# Grove_-_Triple_Color_E-Ink_Display_2_13.net
KiCad netlist of a schematic drawn in EAGLE
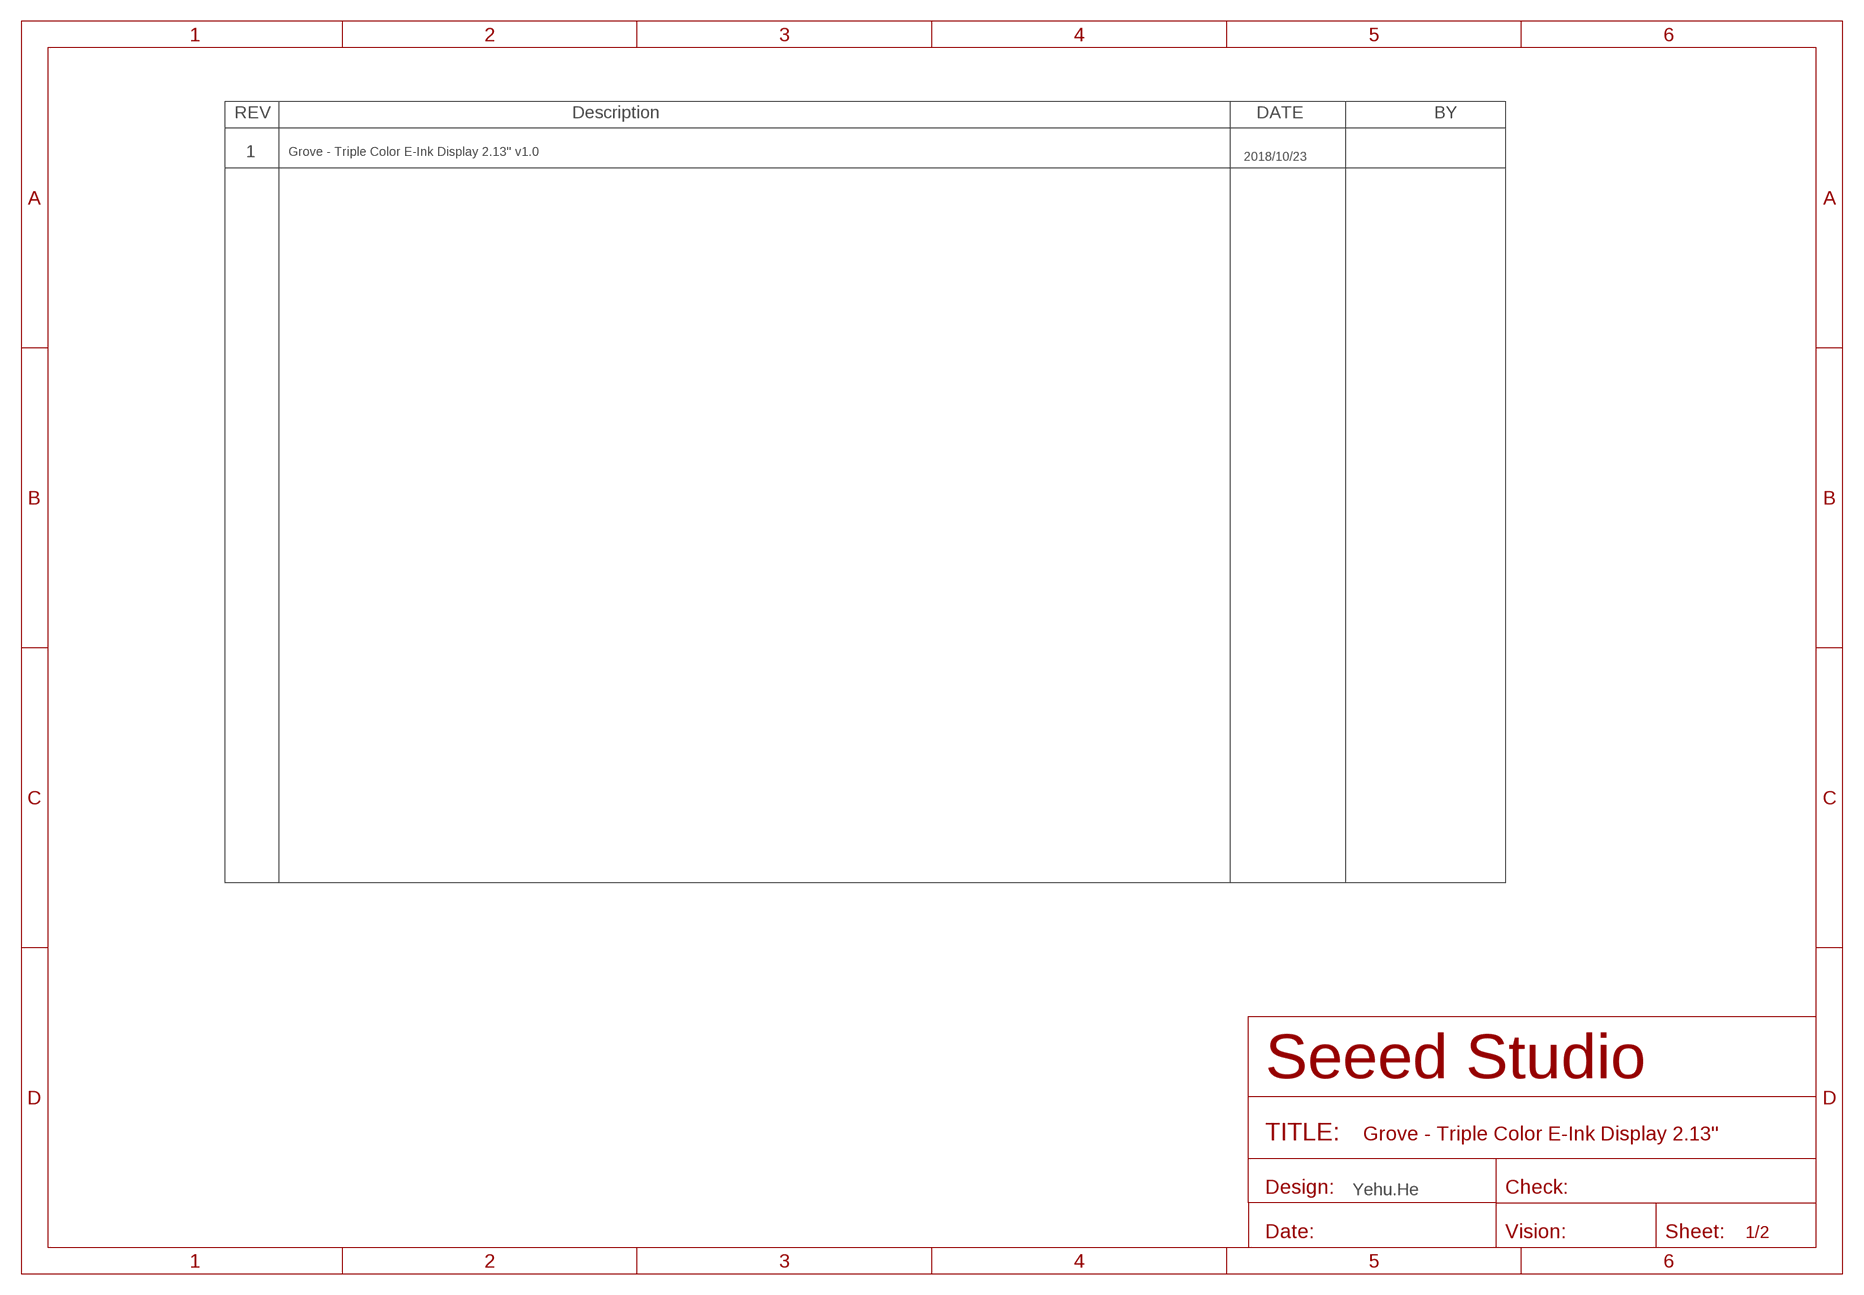
[diagram p0: schematic, sheet 1]
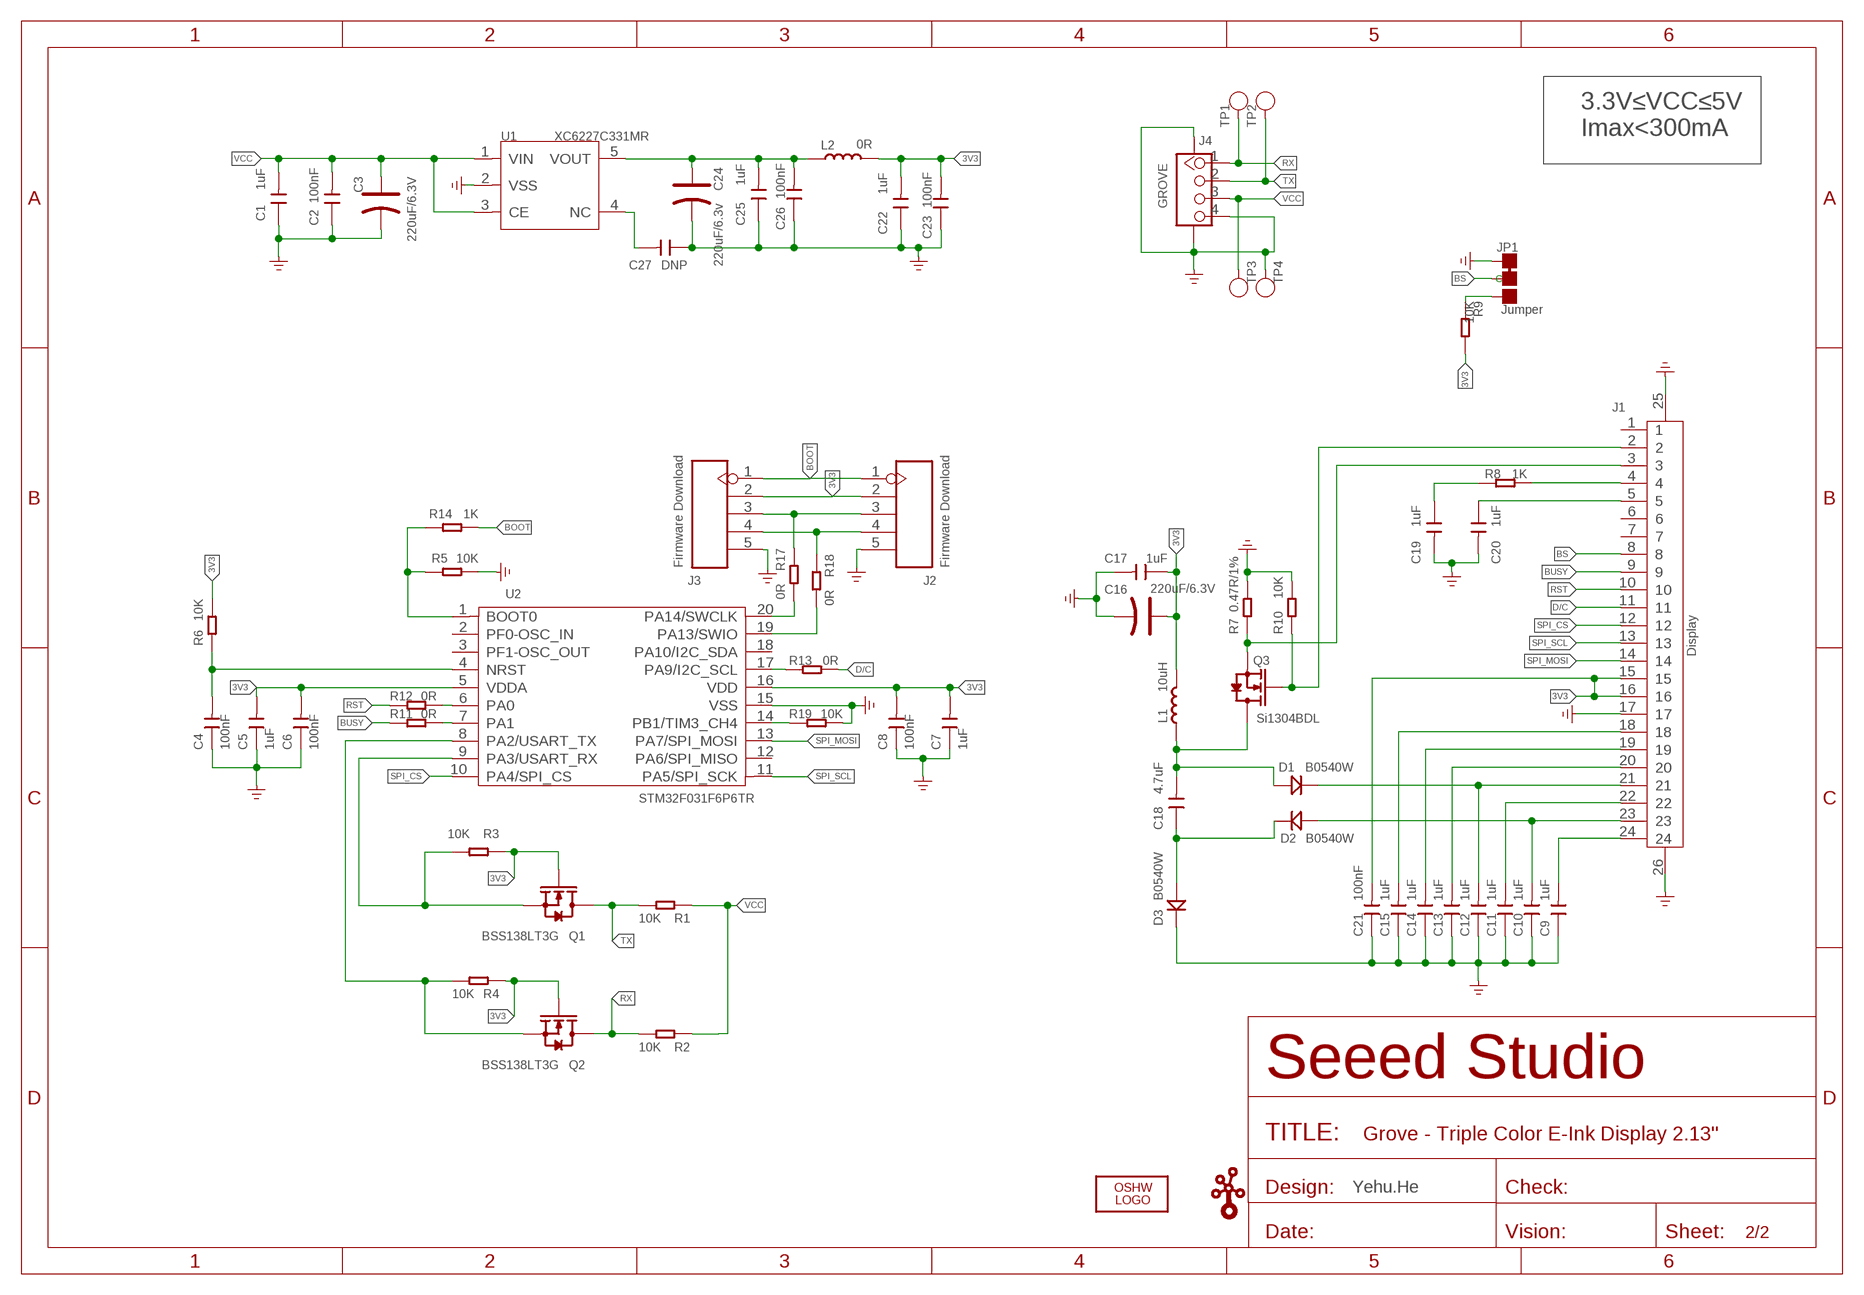
[diagram p1: schematic, sheet 2]

(export (version "E")
  (design (tool "Eeschema 10.0.6"))
  (components
    (comp (ref "C1")
      (value "1uF")
      (footprint "eagle-import:C0603")
      (libsource (lib "eagle-import") (part "CAP-0603"))
    )
    (comp (ref "C2")
      (value "100nF")
      (footprint "eagle-import:C0603")
      (libsource (lib "eagle-import") (part "CAP-0603"))
    )
    (comp (ref "C3")
      (value "220uF/6.3V")
      (footprint "eagle-import:AVX-B")
      (libsource (lib "eagle-import") (part "CAP-POLAR-AVX-B"))
    )
    (comp (ref "C4")
      (value "100nF")
      (footprint "eagle-import:C0603")
      (libsource (lib "eagle-import") (part "CAP-0603"))
    )
    (comp (ref "C5")
      (value "1uF")
      (footprint "eagle-import:C0603")
      (libsource (lib "eagle-import") (part "CAP-0603"))
    )
    (comp (ref "C6")
      (value "100nF")
      (footprint "eagle-import:C0603")
      (libsource (lib "eagle-import") (part "CAP-0603"))
    )
    (comp (ref "C7")
      (value "1uF")
      (footprint "eagle-import:C0603")
      (libsource (lib "eagle-import") (part "CAP-0603"))
    )
    (comp (ref "C8")
      (value "100nF")
      (footprint "eagle-import:C0603")
      (libsource (lib "eagle-import") (part "CAP-0603"))
    )
    (comp (ref "C9")
      (value "1uF")
      (footprint "eagle-import:C0603")
      (libsource (lib "eagle-import") (part "CAP-0603"))
    )
    (comp (ref "C10")
      (value "1uF")
      (footprint "eagle-import:C0603")
      (libsource (lib "eagle-import") (part "CAP-0603"))
    )
    (comp (ref "C11")
      (value "1uF")
      (footprint "eagle-import:C0603")
      (libsource (lib "eagle-import") (part "CAP-0603"))
    )
    (comp (ref "C12")
      (value "1uF")
      (footprint "eagle-import:C0603")
      (libsource (lib "eagle-import") (part "CAP-0603"))
    )
    (comp (ref "C13")
      (value "1uF")
      (footprint "eagle-import:C0603")
      (libsource (lib "eagle-import") (part "CAP-0603"))
    )
    (comp (ref "C14")
      (value "1uF")
      (footprint "eagle-import:C0603")
      (libsource (lib "eagle-import") (part "CAP-0603"))
    )
    (comp (ref "C15")
      (value "1uF")
      (footprint "eagle-import:C0603")
      (libsource (lib "eagle-import") (part "CAP-0603"))
    )
    (comp (ref "C16")
      (value "220uF/6.3V")
      (footprint "eagle-import:AVX-B")
      (libsource (lib "eagle-import") (part "CAP-POLAR-AVX-B"))
    )
    (comp (ref "C17")
      (value "1uF")
      (footprint "eagle-import:C0603")
      (libsource (lib "eagle-import") (part "CAP-0603"))
    )
    (comp (ref "C18")
      (value "4.7uF")
      (footprint "eagle-import:C0805")
      (libsource (lib "eagle-import") (part "CAP-0805"))
    )
    (comp (ref "C19")
      (value "1uF")
      (footprint "eagle-import:C0603")
      (libsource (lib "eagle-import") (part "CAP-0603"))
    )
    (comp (ref "C20")
      (value "1uF")
      (footprint "eagle-import:C0603")
      (libsource (lib "eagle-import") (part "CAP-0603"))
    )
    (comp (ref "C21")
      (value "100nF")
      (footprint "eagle-import:C0603")
      (libsource (lib "eagle-import") (part "CAP-0603"))
    )
    (comp (ref "C22")
      (value "1uF")
      (footprint "eagle-import:C0805")
      (libsource (lib "eagle-import") (part "CAP-0805"))
    )
    (comp (ref "C23")
      (value "100nF")
      (footprint "eagle-import:C0603")
      (libsource (lib "eagle-import") (part "CAP-0603"))
    )
    (comp (ref "C24")
      (value "220uF/6.3v")
      (footprint "eagle-import:AVX-B")
      (libsource (lib "eagle-import") (part "CAP-POLAR-AVX-B"))
    )
    (comp (ref "C25")
      (value "1uF")
      (footprint "eagle-import:C0805")
      (libsource (lib "eagle-import") (part "CAP-0805"))
    )
    (comp (ref "C26")
      (value "100nF")
      (footprint "eagle-import:C0603")
      (libsource (lib "eagle-import") (part "CAP-0603"))
    )
    (comp (ref "C27")
      (value "DNP")
      (footprint "eagle-import:C0603")
      (libsource (lib "eagle-import") (part "CAP-0603"))
    )
    (comp (ref "D1")
      (value "B0540W")
      (footprint "eagle-import:SOD-323")
      (libsource (lib "eagle-import") (part "DIODE'0805'"))
    )
    (comp (ref "D2")
      (value "B0540W")
      (footprint "eagle-import:SOD-323")
      (libsource (lib "eagle-import") (part "DIODE'0805'"))
    )
    (comp (ref "D3")
      (value "B0540W")
      (footprint "eagle-import:SOD-323")
      (libsource (lib "eagle-import") (part "DIODE'0805'"))
    )
    (comp (ref "J1")
      (value "Display")
      (footprint "eagle-import:FPCB24-SMD-0.5-17.6X5.0X2MM")
      (libsource (lib "eagle-import") (part "FPC-CONNECTOR-24P"))
    )
    (comp (ref "J2")
      (value "Firmware Download")
      (footprint "eagle-import:H5-SMD-2.54")
      (libsource (lib "eagle-import") (part "HEADER-5P-SMD2.54"))
    )
    (comp (ref "J3")
      (value "Firmware Download")
      (footprint "eagle-import:H5-SMD-2.54")
      (libsource (lib "eagle-import") (part "HEADER-5P-SMD2.54"))
    )
    (comp (ref "J4")
      (value "GROVE")
      (footprint "eagle-import:HW4-SMD-2.0-90D")
      (libsource (lib "eagle-import") (part "GROVE-CONNECTOR-SMD'90D'"))
    )
    (comp (ref "JP1")
      (value "Jumper")
      (footprint "eagle-import:3P-SMD-SHORT")
      (libsource (lib "eagle-import") (part "JP-3P-SHORT"))
    )
    (comp (ref "L1")
      (value "10uH")
      (footprint "eagle-import:L5040S")
      (libsource (lib "eagle-import") (part "INDUCTOR/FERRITE-BEAD5040S"))
    )
    (comp (ref "L2")
      (value "0R")
      (footprint "eagle-import:L0805")
      (libsource (lib "eagle-import") (part "INDUCTOR/FERRITE-BEAD'0805'"))
    )
    (comp (ref "LOGO2")
      (value "LOGO-OSHW-FILLX0200-NT")
      (footprint "eagle-import:OSHW_FILLX200_NOTEXT")
      (fields (field (name "PARTNO") "DNP"))
      (libsource (lib "eagle-import") (part "LOGO-OSHW-FILLX0200-NT"))
    )
    (comp (ref "Q1")
      (value "BSS138LT3G")
      (footprint "eagle-import:SOT-323")
      (libsource (lib "eagle-import") (part "MOSFET-N'SI1304BDL'"))
    )
    (comp (ref "Q2")
      (value "BSS138LT3G")
      (footprint "eagle-import:SOT-323")
      (libsource (lib "eagle-import") (part "MOSFET-N'SI1304BDL'"))
    )
    (comp (ref "Q3")
      (value "Si1304BDL")
      (footprint "eagle-import:SOT-323")
      (libsource (lib "eagle-import") (part "MOSFET-N'SI1304BDL'"))
    )
    (comp (ref "R1")
      (value "10K")
      (footprint "eagle-import:R0603")
      (libsource (lib "eagle-import") (part "RES-0603"))
    )
    (comp (ref "R2")
      (value "10K")
      (footprint "eagle-import:R0603")
      (libsource (lib "eagle-import") (part "RES-0603"))
    )
    (comp (ref "R3")
      (value "10K")
      (footprint "eagle-import:R0603")
      (libsource (lib "eagle-import") (part "RES-0603"))
    )
    (comp (ref "R4")
      (value "10K")
      (footprint "eagle-import:R0603")
      (libsource (lib "eagle-import") (part "RES-0603"))
    )
    (comp (ref "R5")
      (value "10K")
      (footprint "eagle-import:R0603")
      (libsource (lib "eagle-import") (part "RES-0603"))
    )
    (comp (ref "R6")
      (value "10K")
      (footprint "eagle-import:R0603")
      (libsource (lib "eagle-import") (part "RES-0603"))
    )
    (comp (ref "R7")
      (value "0.47R/1%")
      (footprint "eagle-import:R0603")
      (libsource (lib "eagle-import") (part "RES-0603"))
    )
    (comp (ref "R8")
      (value "1K")
      (footprint "eagle-import:R0603")
      (libsource (lib "eagle-import") (part "RES-0603"))
    )
    (comp (ref "R9")
      (value "10K")
      (footprint "eagle-import:R0603")
      (libsource (lib "eagle-import") (part "RES-0603"))
    )
    (comp (ref "R10")
      (value "10K")
      (footprint "eagle-import:R0603")
      (libsource (lib "eagle-import") (part "RES-0603"))
    )
    (comp (ref "R11")
      (value "0R")
      (footprint "eagle-import:R0603")
      (libsource (lib "eagle-import") (part "RES-0603"))
    )
    (comp (ref "R12")
      (value "0R")
      (footprint "eagle-import:R0603")
      (libsource (lib "eagle-import") (part "RES-0603"))
    )
    (comp (ref "R13")
      (value "0R")
      (footprint "eagle-import:R0603")
      (libsource (lib "eagle-import") (part "RES-0603"))
    )
    (comp (ref "R14")
      (value "1K")
      (footprint "eagle-import:R0603")
      (libsource (lib "eagle-import") (part "RES-0603"))
    )
    (comp (ref "R17")
      (value "0R")
      (footprint "eagle-import:R0603")
      (libsource (lib "eagle-import") (part "RES-0603"))
    )
    (comp (ref "R18")
      (value "0R")
      (footprint "eagle-import:R0603")
      (libsource (lib "eagle-import") (part "RES-0603"))
    )
    (comp (ref "R19")
      (value "10K")
      (footprint "eagle-import:R0603")
      (libsource (lib "eagle-import") (part "RES-0603"))
    )
    (comp (ref "TP1")
      (value "Test")
      (footprint "eagle-import:TP-D45MIL")
      (fields (field (name "PARTNO") "DNP"))
      (libsource (lib "eagle-import") (part "TEST-POINT'4545'"))
    )
    (comp (ref "TP2")
      (value "Test")
      (footprint "eagle-import:TP-D45MIL")
      (fields (field (name "PARTNO") "DNP"))
      (libsource (lib "eagle-import") (part "TEST-POINT'4545'"))
    )
    (comp (ref "TP3")
      (value "Test")
      (footprint "eagle-import:TP-D45MIL")
      (fields (field (name "PARTNO") "DNP"))
      (libsource (lib "eagle-import") (part "TEST-POINT'4545'"))
    )
    (comp (ref "TP4")
      (value "Test")
      (footprint "eagle-import:TP-D45MIL")
      (fields (field (name "PARTNO") "DNP"))
      (libsource (lib "eagle-import") (part "TEST-POINT'4545'"))
    )
    (comp (ref "U$20")
      (value "LOGO-GROVE")
      (footprint "eagle-import:GROVE-SILK-BIG")
      (fields (field (name "PARTNO") "DNP"))
      (libsource (lib "eagle-import") (part "LOGO-GROVE"))
    )
    (comp (ref "U1")
      (value "XC6227C331MR")
      (footprint "eagle-import:SOT-23-5")
      (libsource (lib "eagle-import") (part "PMIC-LDO-XC6210"))
    )
    (comp (ref "U2")
      (value "STM32F031F6P6TR")
      (footprint "eagle-import:TSSOP20-0.65-6.5X4.4MM")
      (libsource (lib "eagle-import") (part "MCU-STM32F030"))
    )
  )
  (nets
    (net (code "1") (name "3V3") (class "Default")
      (node (ref "C16") (pin "+") (pinfunction "+_+") (pintype "passive"))
      (node (ref "C17") (pin "1") (pinfunction "1_1") (pintype "passive"))
      (node (ref "C21") (pin "2") (pinfunction "2_2") (pintype "passive"))
      (node (ref "C22") (pin "2") (pinfunction "2_2") (pintype "passive"))
      (node (ref "C23") (pin "2") (pinfunction "2_2") (pintype "passive"))
      (node (ref "C5") (pin "2") (pinfunction "2_2") (pintype "passive"))
      (node (ref "C6") (pin "2") (pinfunction "2_2") (pintype "passive"))
      (node (ref "C7") (pin "2") (pinfunction "2_2") (pintype "passive"))
      (node (ref "C8") (pin "2") (pinfunction "2_2") (pintype "passive"))
      (node (ref "J1") (pin "15") (pinfunction "15_15") (pintype "bidirectional"))
      (node (ref "J1") (pin "16") (pinfunction "16_16") (pintype "bidirectional"))
      (node (ref "J2") (pin "2") (pinfunction "2_2") (pintype "bidirectional"))
      (node (ref "J3") (pin "2") (pinfunction "2_2") (pintype "bidirectional"))
      (node (ref "L1") (pin "2") (pinfunction "2_2") (pintype "passive"))
      (node (ref "L2") (pin "2") (pinfunction "2_2") (pintype "passive"))
      (node (ref "Q1") (pin "1") (pinfunction "G_1") (pintype "passive"))
      (node (ref "Q2") (pin "1") (pinfunction "G_1") (pintype "passive"))
      (node (ref "R3") (pin "2") (pinfunction "2_2") (pintype "passive"))
      (node (ref "R4") (pin "2") (pinfunction "2_2") (pintype "passive"))
      (node (ref "R6") (pin "1") (pinfunction "1_1") (pintype "passive"))
      (node (ref "R9") (pin "2") (pinfunction "2_2") (pintype "passive"))
      (node (ref "U2") (pin "16") (pinfunction "VDD_16") (pintype "bidirectional"))
      (node (ref "U2") (pin "5") (pinfunction "VDDA_5") (pintype "bidirectional"))
    )
    (net (code "2") (name "BOOT") (class "Default")
      (node (ref "J2") (pin "1") (pinfunction "1_1") (pintype "bidirectional"))
      (node (ref "J3") (pin "1") (pinfunction "1_1") (pintype "bidirectional"))
      (node (ref "R14") (pin "1") (pinfunction "1_1") (pintype "passive"))
    )
    (net (code "3") (name "BS") (class "Default")
      (node (ref "J1") (pin "8") (pinfunction "8_8") (pintype "bidirectional"))
      (node (ref "JP1") (pin "MM") (pinfunction "C_MM") (pintype "bidirectional"))
    )
    (net (code "4") (name "BUSY") (class "Default")
      (node (ref "J1") (pin "9") (pinfunction "9_9") (pintype "bidirectional"))
      (node (ref "R11") (pin "1") (pinfunction "1_1") (pintype "passive"))
    )
    (net (code "5") (name "D{slash}C") (class "Default")
      (node (ref "J1") (pin "11") (pinfunction "11_11") (pintype "bidirectional"))
      (node (ref "R13") (pin "1") (pinfunction "1_1") (pintype "passive"))
    )
    (net (code "6") (name "GND") (class "Default")
      (node (ref "C1") (pin "1") (pinfunction "1_1") (pintype "passive"))
      (node (ref "C10") (pin "1") (pinfunction "1_1") (pintype "passive"))
      (node (ref "C11") (pin "1") (pinfunction "1_1") (pintype "passive"))
      (node (ref "C12") (pin "1") (pinfunction "1_1") (pintype "passive"))
      (node (ref "C13") (pin "1") (pinfunction "1_1") (pintype "passive"))
      (node (ref "C14") (pin "1") (pinfunction "1_1") (pintype "passive"))
      (node (ref "C15") (pin "1") (pinfunction "1_1") (pintype "passive"))
      (node (ref "C16") (pin "-") (pinfunction "-_-") (pintype "passive"))
      (node (ref "C17") (pin "2") (pinfunction "2_2") (pintype "passive"))
      (node (ref "C19") (pin "2") (pinfunction "2_2") (pintype "passive"))
      (node (ref "C2") (pin "1") (pinfunction "1_1") (pintype "passive"))
      (node (ref "C20") (pin "2") (pinfunction "2_2") (pintype "passive"))
      (node (ref "C21") (pin "1") (pinfunction "1_1") (pintype "passive"))
      (node (ref "C22") (pin "1") (pinfunction "1_1") (pintype "passive"))
      (node (ref "C23") (pin "1") (pinfunction "1_1") (pintype "passive"))
      (node (ref "C24") (pin "-") (pinfunction "-_-") (pintype "passive"))
      (node (ref "C25") (pin "1") (pinfunction "1_1") (pintype "passive"))
      (node (ref "C26") (pin "1") (pinfunction "1_1") (pintype "passive"))
      (node (ref "C27") (pin "1") (pinfunction "1_1") (pintype "passive"))
      (node (ref "C3") (pin "-") (pinfunction "-_-") (pintype "passive"))
      (node (ref "C4") (pin "1") (pinfunction "1_1") (pintype "passive"))
      (node (ref "C5") (pin "1") (pinfunction "1_1") (pintype "passive"))
      (node (ref "C6") (pin "1") (pinfunction "1_1") (pintype "passive"))
      (node (ref "C7") (pin "1") (pinfunction "1_1") (pintype "passive"))
      (node (ref "C8") (pin "1") (pinfunction "1_1") (pintype "passive"))
      (node (ref "C9") (pin "1") (pinfunction "1_1") (pintype "passive"))
      (node (ref "D3") (pin "-") (pinfunction "-_-") (pintype "passive"))
      (node (ref "J1") (pin "17") (pinfunction "17_17") (pintype "bidirectional"))
      (node (ref "J1") (pin "25") (pinfunction "P1_25") (pintype "bidirectional"))
      (node (ref "J1") (pin "26") (pinfunction "P2_26") (pintype "bidirectional"))
      (node (ref "J2") (pin "5") (pinfunction "5_5") (pintype "bidirectional"))
      (node (ref "J3") (pin "5") (pinfunction "5_5") (pintype "bidirectional"))
      (node (ref "J4") (pin "4") (pinfunction "4_4") (pintype "bidirectional"))
      (node (ref "J4") (pin "SS1") (pinfunction "SS1_SS1") (pintype "bidirectional"))
      (node (ref "J4") (pin "SS2") (pinfunction "SS2_SS2") (pintype "bidirectional"))
      (node (ref "JP1") (pin "11") (pinfunction "L_11") (pintype "bidirectional"))
      (node (ref "R10") (pin "2") (pinfunction "2_2") (pintype "passive"))
      (node (ref "R19") (pin "1") (pinfunction "1_1") (pintype "passive"))
      (node (ref "R5") (pin "1") (pinfunction "1_1") (pintype "passive"))
      (node (ref "R7") (pin "2") (pinfunction "2_2") (pintype "passive"))
      (node (ref "TP4") (pin "T") (pinfunction "T_T") (pintype "bidirectional"))
      (node (ref "U1") (pin "2") (pinfunction "VSS_2") (pintype "bidirectional"))
      (node (ref "U2") (pin "15") (pinfunction "VSS_15") (pintype "bidirectional"))
    )
    (net (code "7") (name "Net-(C9-Pad2)") (class "Default")
      (node (ref "C9") (pin "2") (pinfunction "2_2") (pintype "passive"))
      (node (ref "J1") (pin "24") (pinfunction "24_24") (pintype "bidirectional"))
    )
    (net (code "8") (name "Net-(C10-Pad2)") (class "Default")
      (node (ref "C10") (pin "2") (pinfunction "2_2") (pintype "passive"))
      (node (ref "D2") (pin "+") (pinfunction "+_+") (pintype "passive"))
      (node (ref "J1") (pin "23") (pinfunction "23_23") (pintype "bidirectional"))
    )
    (net (code "9") (name "Net-(C11-Pad2)") (class "Default")
      (node (ref "C11") (pin "2") (pinfunction "2_2") (pintype "passive"))
      (node (ref "J1") (pin "22") (pinfunction "22_22") (pintype "bidirectional"))
    )
    (net (code "10") (name "Net-(C12-Pad2)") (class "Default")
      (node (ref "C12") (pin "2") (pinfunction "2_2") (pintype "passive"))
      (node (ref "D1") (pin "-") (pinfunction "-_-") (pintype "passive"))
      (node (ref "J1") (pin "21") (pinfunction "21_21") (pintype "bidirectional"))
    )
    (net (code "11") (name "Net-(C13-Pad2)") (class "Default")
      (node (ref "C13") (pin "2") (pinfunction "2_2") (pintype "passive"))
      (node (ref "J1") (pin "20") (pinfunction "20_20") (pintype "bidirectional"))
    )
    (net (code "12") (name "Net-(C14-Pad2)") (class "Default")
      (node (ref "C14") (pin "2") (pinfunction "2_2") (pintype "passive"))
      (node (ref "J1") (pin "19") (pinfunction "19_19") (pintype "bidirectional"))
    )
    (net (code "13") (name "Net-(C15-Pad2)") (class "Default")
      (node (ref "C15") (pin "2") (pinfunction "2_2") (pintype "passive"))
      (node (ref "J1") (pin "18") (pinfunction "18_18") (pintype "bidirectional"))
    )
    (net (code "14") (name "Net-(C18-Pad1)") (class "Default")
      (node (ref "C18") (pin "1") (pinfunction "1_1") (pintype "passive"))
      (node (ref "D2") (pin "-") (pinfunction "-_-") (pintype "passive"))
      (node (ref "D3") (pin "+") (pinfunction "+_+") (pintype "passive"))
    )
    (net (code "15") (name "Net-(C19-Pad1)") (class "Default")
      (node (ref "C19") (pin "1") (pinfunction "1_1") (pintype "passive"))
      (node (ref "R8") (pin "2") (pinfunction "2_2") (pintype "passive"))
    )
    (net (code "16") (name "Net-(C20-Pad1)") (class "Default")
      (node (ref "C20") (pin "1") (pinfunction "1_1") (pintype "passive"))
      (node (ref "J1") (pin "5") (pinfunction "5_5") (pintype "bidirectional"))
    )
    (net (code "17") (name "Net-(J1-Pad4)") (class "Default")
      (node (ref "J1") (pin "4") (pinfunction "4_4") (pintype "bidirectional"))
      (node (ref "R8") (pin "1") (pinfunction "1_1") (pintype "passive"))
    )
    (net (code "18") (name "Net-(J2-Pad3)") (class "Default")
      (node (ref "J2") (pin "3") (pinfunction "3_3") (pintype "bidirectional"))
      (node (ref "J3") (pin "3") (pinfunction "3_3") (pintype "bidirectional"))
      (node (ref "R17") (pin "1") (pinfunction "1_1") (pintype "passive"))
    )
    (net (code "19") (name "Net-(J2-Pad4)") (class "Default")
      (node (ref "J2") (pin "4") (pinfunction "4_4") (pintype "bidirectional"))
      (node (ref "J3") (pin "4") (pinfunction "4_4") (pintype "bidirectional"))
      (node (ref "R18") (pin "1") (pinfunction "1_1") (pintype "passive"))
    )
    (net (code "20") (name "Net-(JP1-R)") (class "Default")
      (node (ref "JP1") (pin "00") (pinfunction "R_00") (pintype "bidirectional"))
      (node (ref "R9") (pin "1") (pinfunction "1_1") (pintype "passive"))
    )
    (net (code "21") (name "Net-(Q1-S)") (class "Default")
      (node (ref "Q1") (pin "2") (pinfunction "S_2") (pintype "passive"))
      (node (ref "R3") (pin "1") (pinfunction "1_1") (pintype "passive"))
      (node (ref "U2") (pin "9") (pinfunction "PA3/USART_RX_9") (pintype "bidirectional"))
    )
    (net (code "22") (name "Net-(Q2-S)") (class "Default")
      (node (ref "Q2") (pin "2") (pinfunction "S_2") (pintype "passive"))
      (node (ref "R4") (pin "1") (pinfunction "1_1") (pintype "passive"))
      (node (ref "U2") (pin "8") (pinfunction "PA2/USART_TX_8") (pintype "bidirectional"))
    )
    (net (code "23") (name "Net-(Q3-D)") (class "Default")
      (node (ref "C18") (pin "2") (pinfunction "2_2") (pintype "passive"))
      (node (ref "D1") (pin "+") (pinfunction "+_+") (pintype "passive"))
      (node (ref "L1") (pin "1") (pinfunction "1_1") (pintype "passive"))
      (node (ref "Q3") (pin "3") (pinfunction "D_3") (pintype "passive"))
    )
    (net (code "24") (name "Net-(Q3-G)") (class "Default")
      (node (ref "J1") (pin "2") (pinfunction "2_2") (pintype "bidirectional"))
      (node (ref "Q3") (pin "1") (pinfunction "G_1") (pintype "passive"))
      (node (ref "R10") (pin "1") (pinfunction "1_1") (pintype "passive"))
    )
    (net (code "25") (name "Net-(Q3-S)") (class "Default")
      (node (ref "J1") (pin "3") (pinfunction "3_3") (pintype "bidirectional"))
      (node (ref "Q3") (pin "2") (pinfunction "S_2") (pintype "passive"))
      (node (ref "R7") (pin "1") (pinfunction "1_1") (pintype "passive"))
    )
    (net (code "26") (name "Net-(U1-NC)") (class "Default")
      (node (ref "C27") (pin "2") (pinfunction "2_2") (pintype "passive"))
      (node (ref "U1") (pin "4") (pinfunction "NC_4") (pintype "bidirectional"))
    )
    (net (code "27") (name "Net-(U1-VOUT)") (class "Default")
      (node (ref "C24") (pin "+") (pinfunction "+_+") (pintype "passive"))
      (node (ref "C25") (pin "2") (pinfunction "2_2") (pintype "passive"))
      (node (ref "C26") (pin "2") (pinfunction "2_2") (pintype "passive"))
      (node (ref "L2") (pin "1") (pinfunction "1_1") (pintype "passive"))
      (node (ref "U1") (pin "5") (pinfunction "VOUT_5") (pintype "bidirectional"))
    )
    (net (code "28") (name "Net-(U2-BOOT0)") (class "Default")
      (node (ref "R14") (pin "2") (pinfunction "2_2") (pintype "passive"))
      (node (ref "R5") (pin "2") (pinfunction "2_2") (pintype "passive"))
      (node (ref "U2") (pin "1") (pinfunction "BOOT0_1") (pintype "bidirectional"))
    )
    (net (code "29") (name "Net-(U2-NRST)") (class "Default")
      (node (ref "C4") (pin "2") (pinfunction "2_2") (pintype "passive"))
      (node (ref "R6") (pin "2") (pinfunction "2_2") (pintype "passive"))
      (node (ref "U2") (pin "4") (pinfunction "NRST_4") (pintype "bidirectional"))
    )
    (net (code "30") (name "Net-(U2-PA0)") (class "Default")
      (node (ref "R12") (pin "2") (pinfunction "2_2") (pintype "passive"))
      (node (ref "U2") (pin "6") (pinfunction "PA0_6") (pintype "bidirectional"))
    )
    (net (code "31") (name "Net-(U2-PA1)") (class "Default")
      (node (ref "R11") (pin "2") (pinfunction "2_2") (pintype "passive"))
      (node (ref "U2") (pin "7") (pinfunction "PA1_7") (pintype "bidirectional"))
    )
    (net (code "32") (name "Net-(U2-PA9{slash}I2C_SCL)") (class "Default")
      (node (ref "R13") (pin "2") (pinfunction "2_2") (pintype "passive"))
      (node (ref "U2") (pin "17") (pinfunction "PA9/I2C_SCL_17") (pintype "bidirectional"))
    )
    (net (code "33") (name "Net-(U2-PA13{slash}SWIO)") (class "Default")
      (node (ref "R18") (pin "2") (pinfunction "2_2") (pintype "passive"))
      (node (ref "U2") (pin "19") (pinfunction "PA13/SWIO_19") (pintype "bidirectional"))
    )
    (net (code "34") (name "Net-(U2-PA14{slash}SWCLK)") (class "Default")
      (node (ref "R17") (pin "2") (pinfunction "2_2") (pintype "passive"))
      (node (ref "U2") (pin "20") (pinfunction "PA14/SWCLK_20") (pintype "bidirectional"))
    )
    (net (code "35") (name "Net-(U2-PB1{slash}TIM3_CH4)") (class "Default")
      (node (ref "R19") (pin "2") (pinfunction "2_2") (pintype "passive"))
      (node (ref "U2") (pin "14") (pinfunction "PB1/TIM3_CH4_14") (pintype "bidirectional"))
    )
    (net (code "36") (name "RST") (class "Default")
      (node (ref "J1") (pin "10") (pinfunction "10_10") (pintype "bidirectional"))
      (node (ref "R12") (pin "1") (pinfunction "1_1") (pintype "passive"))
    )
    (net (code "37") (name "RX") (class "Default")
      (node (ref "J4") (pin "1") (pinfunction "1_1") (pintype "bidirectional"))
      (node (ref "Q2") (pin "3") (pinfunction "D_3") (pintype "passive"))
      (node (ref "R2") (pin "1") (pinfunction "1_1") (pintype "passive"))
      (node (ref "TP1") (pin "T") (pinfunction "T_T") (pintype "bidirectional"))
    )
    (net (code "38") (name "SPI_CS") (class "Default")
      (node (ref "J1") (pin "12") (pinfunction "12_12") (pintype "bidirectional"))
      (node (ref "U2") (pin "10") (pinfunction "PA4/SPI_CS_10") (pintype "bidirectional"))
    )
    (net (code "39") (name "SPI_MOSI") (class "Default")
      (node (ref "J1") (pin "14") (pinfunction "14_14") (pintype "bidirectional"))
      (node (ref "U2") (pin "13") (pinfunction "PA7/SPI_MOSI_13") (pintype "bidirectional"))
    )
    (net (code "40") (name "SPI_SCL") (class "Default")
      (node (ref "J1") (pin "13") (pinfunction "13_13") (pintype "bidirectional"))
      (node (ref "U2") (pin "11") (pinfunction "PA5/SPI_SCK_11") (pintype "bidirectional"))
    )
    (net (code "41") (name "TX") (class "Default")
      (node (ref "J4") (pin "2") (pinfunction "2_2") (pintype "bidirectional"))
      (node (ref "Q1") (pin "3") (pinfunction "D_3") (pintype "passive"))
      (node (ref "R1") (pin "1") (pinfunction "1_1") (pintype "passive"))
      (node (ref "TP2") (pin "T") (pinfunction "T_T") (pintype "bidirectional"))
    )
    (net (code "42") (name "VCC") (class "Default")
      (node (ref "C1") (pin "2") (pinfunction "2_2") (pintype "passive"))
      (node (ref "C2") (pin "2") (pinfunction "2_2") (pintype "passive"))
      (node (ref "C3") (pin "+") (pinfunction "+_+") (pintype "passive"))
      (node (ref "J4") (pin "3") (pinfunction "3_3") (pintype "bidirectional"))
      (node (ref "R1") (pin "2") (pinfunction "2_2") (pintype "passive"))
      (node (ref "R2") (pin "2") (pinfunction "2_2") (pintype "passive"))
      (node (ref "TP3") (pin "T") (pinfunction "T_T") (pintype "bidirectional"))
      (node (ref "U1") (pin "1") (pinfunction "VIN_1") (pintype "bidirectional"))
      (node (ref "U1") (pin "3") (pinfunction "CE_3") (pintype "bidirectional"))
    )
    (net (code "43") (name "unconnected-(J1-Pad1)") (class "Default")
      (node (ref "J1") (pin "1") (pinfunction "1_1") (pintype "bidirectional"))
    )
    (net (code "44") (name "unconnected-(J1-Pad6)") (class "Default")
      (node (ref "J1") (pin "6") (pinfunction "6_6") (pintype "bidirectional"))
    )
    (net (code "45") (name "unconnected-(J1-Pad7)") (class "Default")
      (node (ref "J1") (pin "7") (pinfunction "7_7") (pintype "bidirectional"))
    )
    (net (code "46") (name "unconnected-(U2-PA6{slash}SPI_MISO-Pad12)") (class "Default")
      (node (ref "U2") (pin "12") (pinfunction "PA6/SPI_MISO_12") (pintype "bidirectional"))
    )
    (net (code "47") (name "unconnected-(U2-PA10{slash}I2C_SDA-Pad18)") (class "Default")
      (node (ref "U2") (pin "18") (pinfunction "PA10/I2C_SDA_18") (pintype "bidirectional"))
    )
    (net (code "48") (name "unconnected-(U2-PF0-OSC_IN-Pad2)") (class "Default")
      (node (ref "U2") (pin "2") (pinfunction "PF0-OSC_IN_2") (pintype "bidirectional"))
    )
    (net (code "49") (name "unconnected-(U2-PF1-OSC_OUT-Pad3)") (class "Default")
      (node (ref "U2") (pin "3") (pinfunction "PF1-OSC_OUT_3") (pintype "bidirectional"))
    )
  )
)
